# PIB_Quadcopter_PCB.net
KiCad netlist of a schematic drawn in EAGLE
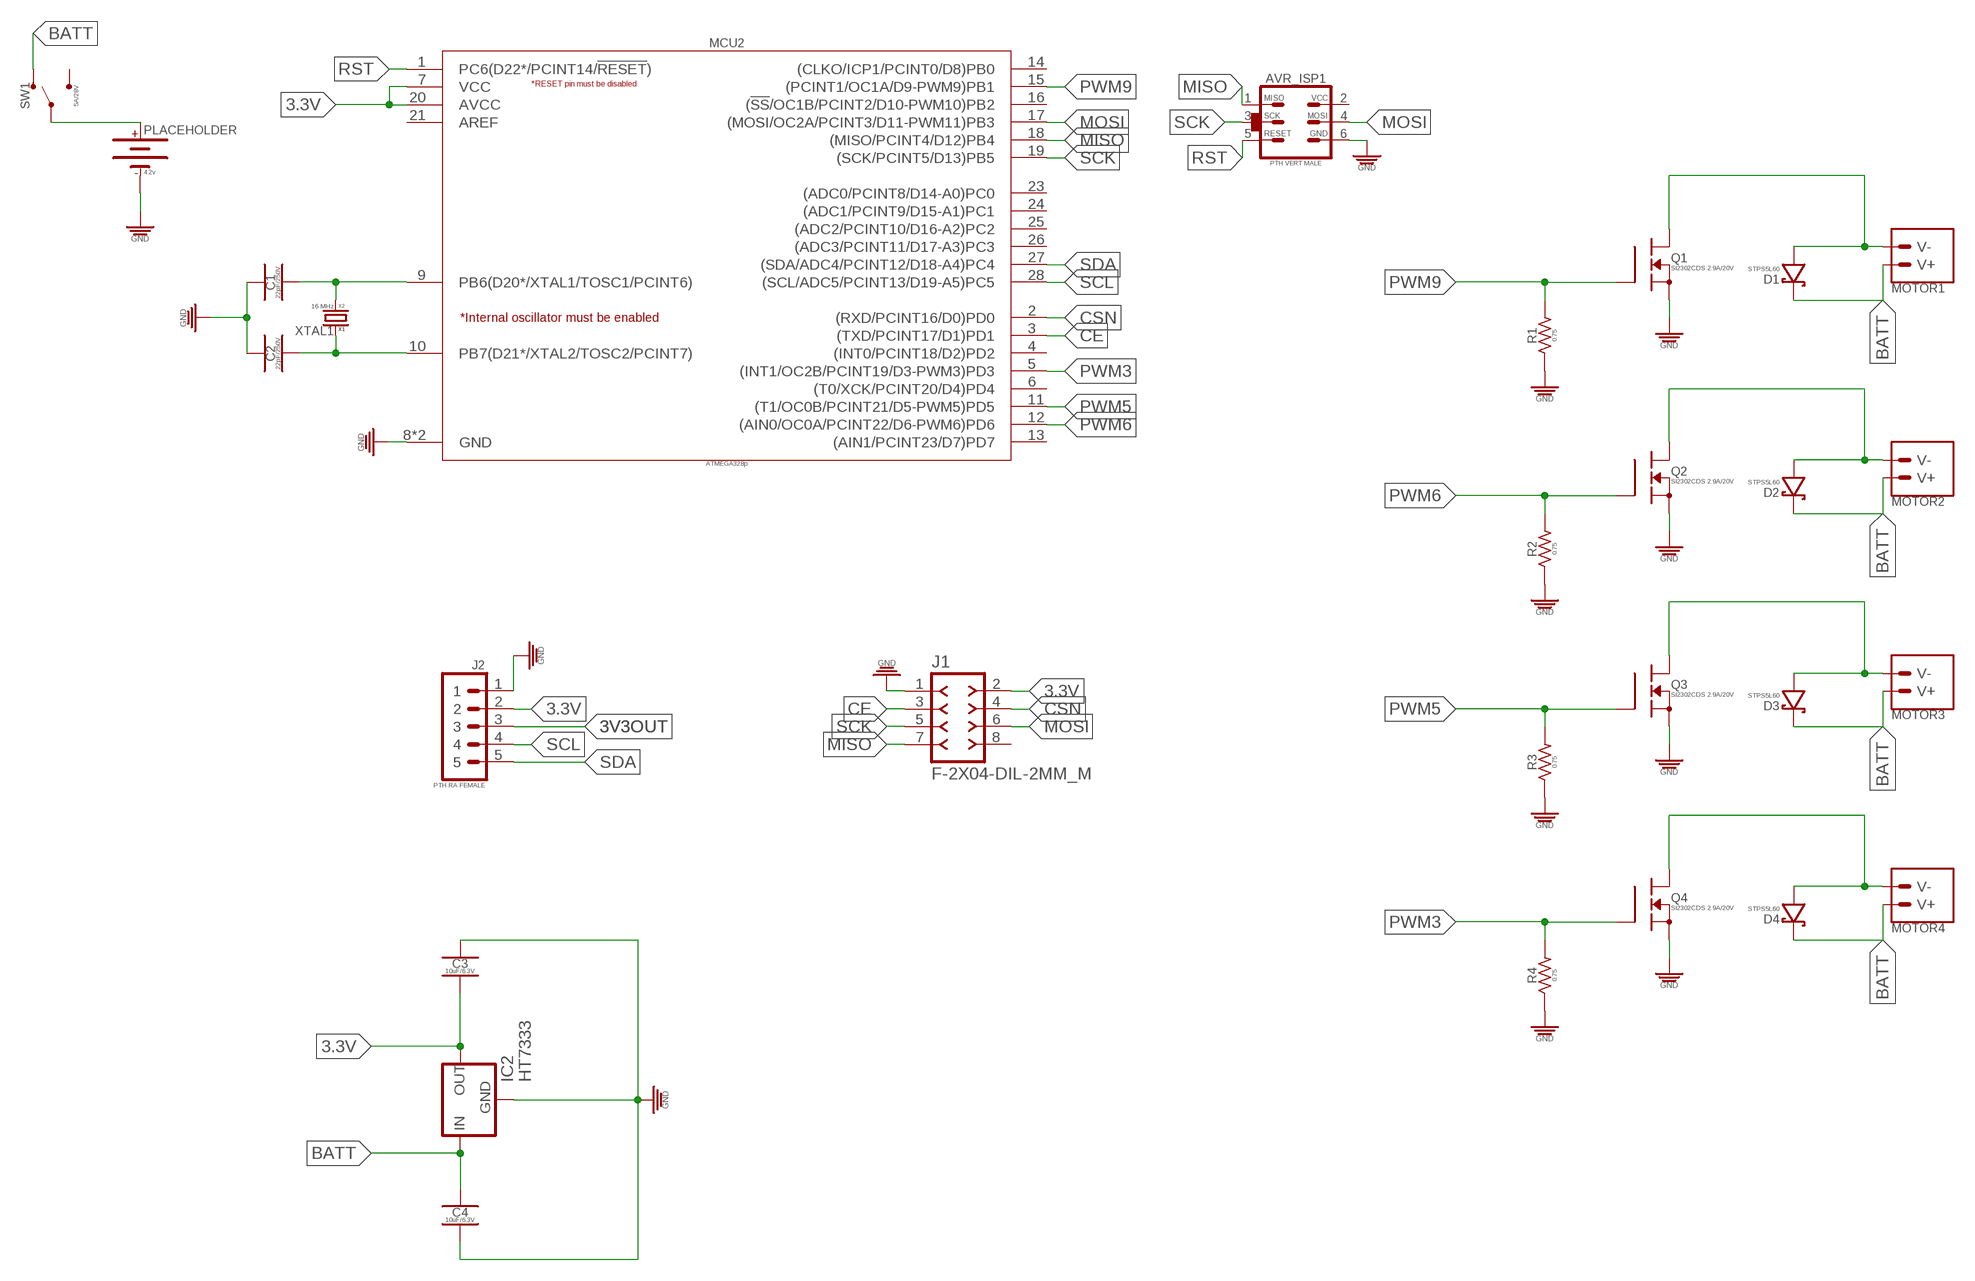
[diagram p0: schematic, sheet 1]

(export (version "E")
  (design (tool "Eeschema 10.0.6"))
  (components
    (comp (ref "AVR_ISP1")
      (value "PTH VERT MALE")
      (footprint "eagle-import:HDRV6W64P254_2X3_762X483X838B_AVR-ISP")
      (fields (field (name "MFR") "Amphenol FCI") (field (name "MPN") "67997-206HLF"))
      (libsource (lib "eagle-import") (part "AVR_SPI_PRG_6_PTH_VERT_MALE_2.54MM"))
    )
    (comp (ref "C1")
      (value "22pF/250V")
      (footprint "eagle-import:CAPC1608X95")
      (fields (field (name "MFR") "Yageo") (field (name "MPN") "AC0603JRNPOYBN220"))
      (libsource (lib "eagle-import") (part "22PF_CER_SMD-0603_250V-5%"))
    )
    (comp (ref "C2")
      (value "22pF/250V")
      (footprint "eagle-import:CAPC1608X95")
      (fields (field (name "MFR") "Yageo") (field (name "MPN") "AC0603JRNPOYBN220"))
      (libsource (lib "eagle-import") (part "22PF_CER_SMD-0603_250V-5%"))
    )
    (comp (ref "C3")
      (value "10uF/6.3V")
      (footprint "eagle-import:CAPC1005X55_SMD-0402")
      (fields
        (field (name "MFR") "Murata Electronics North America")
        (field (name "MPN") "GRM155C80J106ME11D")
      )
      (libsource (lib "eagle-import") (part "10UF_CER_SMD-0402_6.3V-20%"))
    )
    (comp (ref "C4")
      (value "10uF/6.3V")
      (footprint "eagle-import:CAPC1005X55_SMD-0402")
      (fields
        (field (name "MFR") "Murata Electronics North America")
        (field (name "MPN") "GRM155C80J106ME11D")
      )
      (libsource (lib "eagle-import") (part "10UF_CER_SMD-0402_6.3V-20%"))
    )
    (comp (ref "D1")
      (value "STPS5L60")
      (footprint "eagle-import:D0-201AD")
      (fields (field (name "MFR") "STMicroelectronics") (field (name "CREATOR") "MrSwirlyEyes"))
      (libsource (lib "eagle-import") (part "SCHOTTKY_POWER-SCHOTTKY_5A-60V_D0-201AD"))
    )
    (comp (ref "D2")
      (value "STPS5L60")
      (footprint "eagle-import:D0-201AD")
      (fields (field (name "MFR") "STMicroelectronics") (field (name "CREATOR") "MrSwirlyEyes"))
      (libsource (lib "eagle-import") (part "SCHOTTKY_POWER-SCHOTTKY_5A-60V_D0-201AD"))
    )
    (comp (ref "D3")
      (value "STPS5L60")
      (footprint "eagle-import:D0-201AD")
      (fields (field (name "MFR") "STMicroelectronics") (field (name "CREATOR") "MrSwirlyEyes"))
      (libsource (lib "eagle-import") (part "SCHOTTKY_POWER-SCHOTTKY_5A-60V_D0-201AD"))
    )
    (comp (ref "D4")
      (value "STPS5L60")
      (footprint "eagle-import:D0-201AD")
      (fields (field (name "MFR") "STMicroelectronics") (field (name "CREATOR") "MrSwirlyEyes"))
      (libsource (lib "eagle-import") (part "SCHOTTKY_POWER-SCHOTTKY_5A-60V_D0-201AD"))
    )
    (comp (ref "IC2")
      (value "HT7333")
      (footprint "eagle-import:SOT-89")
      (libsource (lib "eagle-import") (part "HT7333"))
    )
    (comp (ref "J1")
      (value "F-2X04-DIL-2MM_M")
      (footprint "eagle-import:DIL-2MM-2X04_M")
      (libsource (lib "eagle-import") (part "F-2X04-DIL-2MM_M"))
    )
    (comp (ref "J2")
      (value "PTH RA FEMALE")
      (footprint "eagle-import:HDRRAR5W60P254_1X5_1320X850X274B")
      (fields (field (name "MFR") "Sullins Connector Solutions") (field (name "MPN") "PPTC051LGBN-RC"))
      (libsource (lib "eagle-import") (part "1X05_PTH_RA_FEMALE_2.54MM"))
    )
    (comp (ref "MCU2")
      (value "ATMEGA328p")
      (footprint "eagle-import:DIP762W53P254L3467H472Q28B")
      (fields (field (name "MFR") "Microchip Technology") (field (name "MPN") "ATMEGA328P-PU"))
      (libsource (lib "eagle-import") (part "ATMEGA328P-28_28-PDIP_8BIT_32KB"))
    )
    (comp (ref "MOTOR1")
      (value "MOTOR_PADSPTH")
      (footprint "eagle-import:CONNECTOR_MOTOR")
      (libsource (lib "eagle-import") (part "MOTOR_PADSPTH"))
    )
    (comp (ref "MOTOR2")
      (value "MOTOR_PADSPTH")
      (footprint "eagle-import:CONNECTOR_MOTOR")
      (libsource (lib "eagle-import") (part "MOTOR_PADSPTH"))
    )
    (comp (ref "MOTOR3")
      (value "MOTOR_PADSPTH")
      (footprint "eagle-import:CONNECTOR_MOTOR")
      (libsource (lib "eagle-import") (part "MOTOR_PADSPTH"))
    )
    (comp (ref "MOTOR4")
      (value "MOTOR_PADSPTH")
      (footprint "eagle-import:CONNECTOR_MOTOR")
      (libsource (lib "eagle-import") (part "MOTOR_PADSPTH"))
    )
    (comp (ref "PLACEHOLDER")
      (value "4.2v")
      (footprint "eagle-import:BATTERY_MOLEX-89400_VERT_PITCH-2MM")
      (fields (field (name "MFR") "Molex, LLC") (field (name "MPN") "0894000220"))
      (libsource (lib "eagle-import") (part "BATTERY-CONNECTOR_MOLEX_89400_VERT-MALE_PITCH-2MM"))
    )
    (comp (ref "Q1")
      (value "SI2302CDS 2.9A/20V")
      (footprint "eagle-import:SOT95P287X112-3")
      (fields (field (name "MFR") "Vishay Siliconix") (field (name "MPN") "SI2302DDS-T1-GE3"))
      (libsource (lib "eagle-import") (part "MOSFET_N-CHANNEL_SI2302CDS_2.9A-20V-0.057OHM_"))
    )
    (comp (ref "Q2")
      (value "SI2302CDS 2.9A/20V")
      (footprint "eagle-import:SOT95P287X112-3")
      (fields (field (name "MFR") "Vishay Siliconix") (field (name "MPN") "SI2302DDS-T1-GE3"))
      (libsource (lib "eagle-import") (part "MOSFET_N-CHANNEL_SI2302CDS_2.9A-20V-0.057OHM_"))
    )
    (comp (ref "Q3")
      (value "SI2302CDS 2.9A/20V")
      (footprint "eagle-import:SOT95P287X112-3")
      (fields (field (name "MFR") "Vishay Siliconix") (field (name "MPN") "SI2302DDS-T1-GE3"))
      (libsource (lib "eagle-import") (part "MOSFET_N-CHANNEL_SI2302CDS_2.9A-20V-0.057OHM_"))
    )
    (comp (ref "Q4")
      (value "SI2302CDS 2.9A/20V")
      (footprint "eagle-import:SOT95P287X112-3")
      (fields (field (name "MFR") "Vishay Siliconix") (field (name "MPN") "SI2302DDS-T1-GE3"))
      (libsource (lib "eagle-import") (part "MOSFET_N-CHANNEL_SI2302CDS_2.9A-20V-0.057OHM_"))
    )
    (comp (ref "R1")
      (value "0.75")
      (footprint "eagle-import:RESC1608X65_SMD-0603")
      (fields (field (name "MFR") "TE Connectivity Passive Product") (field (name "MPN") "RLP73K1JR75JTD"))
      (libsource (lib "eagle-import") (part "0.75Ω_SMD-0603_1/8W-5%"))
    )
    (comp (ref "R2")
      (value "0.75")
      (footprint "eagle-import:RESC1608X65_SMD-0603")
      (fields (field (name "MFR") "TE Connectivity Passive Product") (field (name "MPN") "RLP73K1JR75JTD"))
      (libsource (lib "eagle-import") (part "0.75Ω_SMD-0603_1/8W-5%"))
    )
    (comp (ref "R3")
      (value "0.75")
      (footprint "eagle-import:RESC1608X65_SMD-0603")
      (fields (field (name "MFR") "TE Connectivity Passive Product") (field (name "MPN") "RLP73K1JR75JTD"))
      (libsource (lib "eagle-import") (part "0.75Ω_SMD-0603_1/8W-5%"))
    )
    (comp (ref "R4")
      (value "0.75")
      (footprint "eagle-import:RESC1608X65_SMD-0603")
      (fields (field (name "MFR") "TE Connectivity Passive Product") (field (name "MPN") "RLP73K1JR75JTD"))
      (libsource (lib "eagle-import") (part "0.75Ω_SMD-0603_1/8W-5%"))
    )
    (comp (ref "SW1")
      (value "5A/28V")
      (footprint "eagle-import:SW_TOGGLE_SPDT_5A-28V_13L-7W")
      (fields (field (name "MFR") "E-Switch") (field (name "MPN") "100SP1T1B4M2QE"))
      (libsource (lib "eagle-import") (part "SWITCH_SPDT_VERT_PTH_5A-28V_13L-7W_"))
    )
    (comp (ref "XTAL1")
      (value "16 MHz")
      (footprint "eagle-import:HC-49_US")
      (fields (field (name "MFR") "Abracon LLC") (field (name "MPN") "ABL-16.000MHZ-B2"))
      (libsource (lib "eagle-import") (part "CRYSTAL_ABL_16MHZ_18PF"))
    )
  )
  (nets
    (net (code "1") (name "3.3V") (class "Default")
      (node (ref "C3") (pin "2") (pinfunction "2_2") (pintype "passive"))
      (node (ref "IC2") (pin "1") (pinfunction "OUT_1") (pintype "passive"))
      (node (ref "J1") (pin "2") (pinfunction "2_2") (pintype "passive"))
      (node (ref "J2") (pin "2") (pinfunction "2_2") (pintype "passive"))
      (node (ref "MCU2") (pin "20") (pinfunction "AVCC_20") (pintype "power_in"))
      (node (ref "MCU2") (pin "7") (pinfunction "VCC_7") (pintype "power_in"))
    )
    (net (code "2") (name "3V3OUT") (class "Default")
      (node (ref "J2") (pin "3") (pinfunction "3_3") (pintype "passive"))
    )
    (net (code "3") (name "BATT") (class "Default")
      (node (ref "C4") (pin "1") (pinfunction "1_1") (pintype "passive"))
      (node (ref "D1") (pin "K") (pinfunction "A_K") (pintype "passive"))
      (node (ref "D2") (pin "K") (pinfunction "A_K") (pintype "passive"))
      (node (ref "D3") (pin "K") (pinfunction "A_K") (pintype "passive"))
      (node (ref "D4") (pin "K") (pinfunction "A_K") (pintype "passive"))
      (node (ref "IC2") (pin "3") (pinfunction "IN_3") (pintype "input"))
      (node (ref "IC2") (pin "4") (pinfunction "IN_4") (pintype "input"))
      (node (ref "MOTOR1") (pin "+") (pinfunction "V+_+") (pintype "bidirectional"))
      (node (ref "MOTOR2") (pin "+") (pinfunction "V+_+") (pintype "bidirectional"))
      (node (ref "MOTOR3") (pin "+") (pinfunction "V+_+") (pintype "bidirectional"))
      (node (ref "MOTOR4") (pin "+") (pinfunction "V+_+") (pintype "bidirectional"))
      (node (ref "SW1") (pin "S1") (pinfunction "S1_S1") (pintype "passive"))
    )
    (net (code "4") (name "CE") (class "Default")
      (node (ref "J1") (pin "3") (pinfunction "3_3") (pintype "passive"))
      (node (ref "MCU2") (pin "3") (pinfunction "(TXD/PCINT17/D1)PD1_3") (pintype "bidirectional"))
    )
    (net (code "5") (name "CSN") (class "Default")
      (node (ref "J1") (pin "4") (pinfunction "4_4") (pintype "passive"))
      (node (ref "MCU2") (pin "2") (pinfunction "(RXD/PCINT16/D0)PD0_2") (pintype "bidirectional"))
    )
    (net (code "6") (name "GND") (class "Default")
      (node (ref "AVR_ISP1") (pin "GND") (pinfunction "GND_GND") (pintype "power_in"))
      (node (ref "C1") (pin "1") (pinfunction "1_1") (pintype "passive"))
      (node (ref "C2") (pin "1") (pinfunction "1_1") (pintype "passive"))
      (node (ref "C3") (pin "1") (pinfunction "1_1") (pintype "passive"))
      (node (ref "C4") (pin "2") (pinfunction "2_2") (pintype "passive"))
      (node (ref "IC2") (pin "2") (pinfunction "GND_2") (pintype "input"))
      (node (ref "J1") (pin "1") (pinfunction "1_1") (pintype "passive"))
      (node (ref "J2") (pin "1") (pinfunction "1_1") (pintype "passive"))
      (node (ref "MCU2") (pin "22") (pinfunction "GND_22") (pintype "power_in"))
      (node (ref "MCU2") (pin "8") (pinfunction "GND_8") (pintype "power_in"))
      (node (ref "PLACEHOLDER") (pin "-") (pinfunction "-_-") (pintype "power_in"))
      (node (ref "Q1") (pin "2") (pinfunction "S_2") (pintype "passive"))
      (node (ref "Q2") (pin "2") (pinfunction "S_2") (pintype "passive"))
      (node (ref "Q3") (pin "2") (pinfunction "S_2") (pintype "passive"))
      (node (ref "Q4") (pin "2") (pinfunction "S_2") (pintype "passive"))
      (node (ref "R1") (pin "1") (pinfunction "1_1") (pintype "passive"))
      (node (ref "R2") (pin "1") (pinfunction "1_1") (pintype "passive"))
      (node (ref "R3") (pin "1") (pinfunction "1_1") (pintype "passive"))
      (node (ref "R4") (pin "1") (pinfunction "1_1") (pintype "passive"))
    )
    (net (code "7") (name "MISO") (class "Default")
      (node (ref "AVR_ISP1") (pin "MISO") (pinfunction "MISO_MISO") (pintype "bidirectional"))
      (node (ref "J1") (pin "7") (pinfunction "7_7") (pintype "passive"))
      (node (ref "MCU2") (pin "18") (pinfunction "(MISO/PCINT4/D12)PB4_18") (pintype "bidirectional"))
    )
    (net (code "8") (name "MOSI") (class "Default")
      (node (ref "AVR_ISP1") (pin "MOSI") (pinfunction "MOSI_MOSI") (pintype "bidirectional"))
      (node (ref "J1") (pin "6") (pinfunction "6_6") (pintype "passive"))
      (node (ref "MCU2") (pin "17") (pinfunction "(MOSI/OC2A/PCINT3/D11-PWM11)PB3_17") (pintype "bidirectional"))
    )
    (net (code "9") (name "Net-(D1-K)") (class "Default")
      (node (ref "D1") (pin "A") (pinfunction "K_A") (pintype "passive"))
      (node (ref "MOTOR1") (pin "-") (pinfunction "V-_-") (pintype "bidirectional"))
      (node (ref "Q1") (pin "3") (pinfunction "D_3") (pintype "passive"))
    )
    (net (code "10") (name "Net-(D2-K)") (class "Default")
      (node (ref "D2") (pin "A") (pinfunction "K_A") (pintype "passive"))
      (node (ref "MOTOR2") (pin "-") (pinfunction "V-_-") (pintype "bidirectional"))
      (node (ref "Q2") (pin "3") (pinfunction "D_3") (pintype "passive"))
    )
    (net (code "11") (name "Net-(D3-K)") (class "Default")
      (node (ref "D3") (pin "A") (pinfunction "K_A") (pintype "passive"))
      (node (ref "MOTOR3") (pin "-") (pinfunction "V-_-") (pintype "bidirectional"))
      (node (ref "Q3") (pin "3") (pinfunction "D_3") (pintype "passive"))
    )
    (net (code "12") (name "Net-(D4-K)") (class "Default")
      (node (ref "D4") (pin "A") (pinfunction "K_A") (pintype "passive"))
      (node (ref "MOTOR4") (pin "-") (pinfunction "V-_-") (pintype "bidirectional"))
      (node (ref "Q4") (pin "3") (pinfunction "D_3") (pintype "passive"))
    )
    (net (code "13") (name "Net-(MCU2-PB6(D20*{slash}XTAL1{slash}TOSC1{slash}PCINT6))") (class "Default")
      (node (ref "C1") (pin "2") (pinfunction "2_2") (pintype "passive"))
      (node (ref "MCU2") (pin "9") (pinfunction "PB6(D20*/XTAL1/TOSC1/PCINT6)_9") (pintype "bidirectional"))
      (node (ref "XTAL1") (pin "P$2") (pinfunction "XTAL2_P$2") (pintype "passive"))
    )
    (net (code "14") (name "Net-(MCU2-PB7(D21*{slash}XTAL2{slash}TOSC2{slash}PCINT7))") (class "Default")
      (node (ref "C2") (pin "2") (pinfunction "2_2") (pintype "passive"))
      (node (ref "MCU2") (pin "10") (pinfunction "PB7(D21*/XTAL2/TOSC2/PCINT7)_10") (pintype "bidirectional"))
      (node (ref "XTAL1") (pin "P$1") (pinfunction "XTAL1_P$1") (pintype "passive"))
    )
    (net (code "15") (name "Net-(PLACEHOLDER-Pad+)") (class "Default")
      (node (ref "PLACEHOLDER") (pin "+") (pinfunction "+_+") (pintype "power_in"))
      (node (ref "SW1") (pin "P") (pinfunction "P_P") (pintype "passive"))
    )
    (net (code "16") (name "PWM3") (class "Default")
      (node (ref "MCU2") (pin "5") (pinfunction "(INT1/OC2B/PCINT19/D3-PWM3)PD3_5") (pintype "bidirectional"))
      (node (ref "Q4") (pin "1") (pinfunction "G_1") (pintype "passive"))
      (node (ref "R4") (pin "2") (pinfunction "2_2") (pintype "passive"))
    )
    (net (code "17") (name "PWM5") (class "Default")
      (node (ref "MCU2") (pin "11") (pinfunction "(T1/OC0B/PCINT21/D5-PWM5)PD5_11") (pintype "bidirectional"))
      (node (ref "Q3") (pin "1") (pinfunction "G_1") (pintype "passive"))
      (node (ref "R3") (pin "2") (pinfunction "2_2") (pintype "passive"))
    )
    (net (code "18") (name "PWM6") (class "Default")
      (node (ref "MCU2") (pin "12") (pinfunction "(AIN0/OC0A/PCINT22/D6-PWM6)PD6_12") (pintype "bidirectional"))
      (node (ref "Q2") (pin "1") (pinfunction "G_1") (pintype "passive"))
      (node (ref "R2") (pin "2") (pinfunction "2_2") (pintype "passive"))
    )
    (net (code "19") (name "PWM9") (class "Default")
      (node (ref "MCU2") (pin "15") (pinfunction "(PCINT1/OC1A/D9-PWM9)PB1_15") (pintype "bidirectional"))
      (node (ref "Q1") (pin "1") (pinfunction "G_1") (pintype "passive"))
      (node (ref "R1") (pin "2") (pinfunction "2_2") (pintype "passive"))
    )
    (net (code "20") (name "RST") (class "Default")
      (node (ref "AVR_ISP1") (pin "RESET") (pinfunction "RESET_RESET") (pintype "bidirectional"))
      (node (ref "MCU2") (pin "1") (pinfunction "PC6(D22*/PCINT14/~{RESET})_1") (pintype "bidirectional"))
    )
    (net (code "21") (name "SCK") (class "Default")
      (node (ref "AVR_ISP1") (pin "SCK") (pinfunction "SCK_SCK") (pintype "bidirectional"))
      (node (ref "J1") (pin "5") (pinfunction "5_5") (pintype "passive"))
      (node (ref "MCU2") (pin "19") (pinfunction "(SCK/PCINT5/D13)PB5_19") (pintype "bidirectional"))
    )
    (net (code "22") (name "SCL") (class "Default")
      (node (ref "J2") (pin "4") (pinfunction "4_4") (pintype "passive"))
      (node (ref "MCU2") (pin "28") (pinfunction "(SCL/ADC5/PCINT13/D19-A5)PC5_28") (pintype "bidirectional"))
    )
    (net (code "23") (name "SDA") (class "Default")
      (node (ref "J2") (pin "5") (pinfunction "5_5") (pintype "passive"))
      (node (ref "MCU2") (pin "27") (pinfunction "(SDA/ADC4/PCINT12/D18-A4)PC4_27") (pintype "bidirectional"))
    )
    (net (code "24") (name "unconnected-(AVR_ISP1-PadVCC)") (class "Default")
      (node (ref "AVR_ISP1") (pin "VCC") (pinfunction "VCC_VCC") (pintype "no_connect"))
    )
    (net (code "25") (name "unconnected-(J1-Pad8)") (class "Default")
      (node (ref "J1") (pin "8") (pinfunction "8_8") (pintype "passive"))
    )
    (net (code "26") (name "unconnected-(MCU2-(ADC0{slash}PCINT8{slash}D14-A0)PC0-Pad23)") (class "Default")
      (node (ref "MCU2") (pin "23") (pinfunction "(ADC0/PCINT8/D14-A0)PC0_23") (pintype "bidirectional"))
    )
    (net (code "27") (name "unconnected-(MCU2-(ADC1{slash}PCINT9{slash}D15-A1)PC1-Pad24)") (class "Default")
      (node (ref "MCU2") (pin "24") (pinfunction "(ADC1/PCINT9/D15-A1)PC1_24") (pintype "bidirectional"))
    )
    (net (code "28") (name "unconnected-(MCU2-(ADC2{slash}PCINT10{slash}D16-A2)PC2-Pad25)") (class "Default")
      (node (ref "MCU2") (pin "25") (pinfunction "(ADC2/PCINT10/D16-A2)PC2_25") (pintype "bidirectional"))
    )
    (net (code "29") (name "unconnected-(MCU2-(ADC3{slash}PCINT11{slash}D17-A3)PC3-Pad26)") (class "Default")
      (node (ref "MCU2") (pin "26") (pinfunction "(ADC3/PCINT11/D17-A3)PC3_26") (pintype "bidirectional"))
    )
    (net (code "30") (name "unconnected-(MCU2-(AIN1{slash}PCINT23{slash}D7)PD7-Pad13)") (class "Default")
      (node (ref "MCU2") (pin "13") (pinfunction "(AIN1/PCINT23/D7)PD7_13") (pintype "bidirectional"))
    )
    (net (code "31") (name "unconnected-(MCU2-(CLKO{slash}ICP1{slash}PCINT0{slash}D8)PB0-Pad14)") (class "Default")
      (node (ref "MCU2") (pin "14") (pinfunction "(CLKO/ICP1/PCINT0/D8)PB0_14") (pintype "bidirectional"))
    )
    (net (code "32") (name "unconnected-(MCU2-(INT0{slash}PCINT18{slash}D2)PD2-Pad4)") (class "Default")
      (node (ref "MCU2") (pin "4") (pinfunction "(INT0/PCINT18/D2)PD2_4") (pintype "bidirectional"))
    )
    (net (code "33") (name "unconnected-(MCU2-(T0{slash}XCK{slash}PCINT20{slash}D4)PD4-Pad6)") (class "Default")
      (node (ref "MCU2") (pin "6") (pinfunction "(T0/XCK/PCINT20/D4)PD4_6") (pintype "bidirectional"))
    )
    (net (code "34") (name "unconnected-(MCU2-(~{SS}{slash}OC1B{slash}PCINT2{slash}D10-PWM10)PB2-Pad16)") (class "Default")
      (node (ref "MCU2") (pin "16") (pinfunction "(~{SS}/OC1B/PCINT2/D10-PWM10)PB2_16") (pintype "bidirectional"))
    )
    (net (code "35") (name "unconnected-(MCU2-AREF-Pad21)") (class "Default")
      (node (ref "MCU2") (pin "21") (pinfunction "AREF_21") (pintype "passive"))
    )
    (net (code "36") (name "unconnected-(SW1-PadS2)") (class "Default")
      (node (ref "SW1") (pin "S2") (pinfunction "S2_S2") (pintype "passive"))
    )
  )
)
